# power_supply.net
KiCad netlist of a schematic drawn in Altium Designer
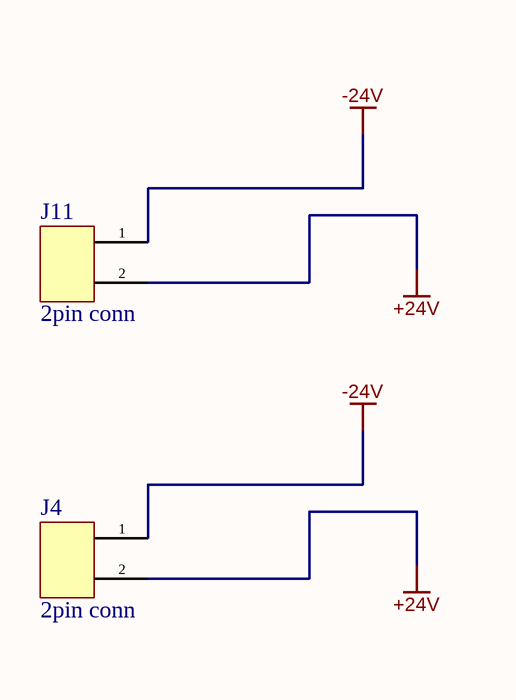
[diagram p0: power_supply.SchDoc]

(export (version "E")
  (design (tool "Eeschema 10.0.6"))
  (components
    (comp (ref "J4")
      (value "2pin conn")
      (footprint "2pin_0.1in")
      (description "CONN HEADER VERT 2POS 2.54MM")
      (fields
        (field (name "MANUFACTURER") "TE Connectivity")
        (field (name "MANUFACTURER PART NUMBER") "640456-2")
      )
      (libsource (lib "current_sense") (part "640456-2"))
    )
    (comp (ref "J11")
      (value "2pin conn")
      (footprint "2pin_0.1in")
      (description "CONN HEADER VERT 2POS 2.54MM")
      (fields
        (field (name "MANUFACTURER") "TE Connectivity")
        (field (name "MANUFACTURER PART NUMBER") "640456-2")
      )
      (libsource (lib "current_sense") (part "640456-2"))
    )
  )
  (nets
    (net (code "1") (name "+24V") (class "Default")
      (node (ref "J11") (pin "2") (pinfunction "2_2") (pintype "power_in"))
      (node (ref "J4") (pin "2") (pinfunction "2_2") (pintype "power_in"))
    )
    (net (code "2") (name "-24V") (class "Default")
      (node (ref "J11") (pin "1") (pinfunction "1_1") (pintype "power_in"))
      (node (ref "J4") (pin "1") (pinfunction "1_1") (pintype "power_in"))
    )
  )
)
